# starduino.net
KiCad netlist of a schematic drawn in EAGLE
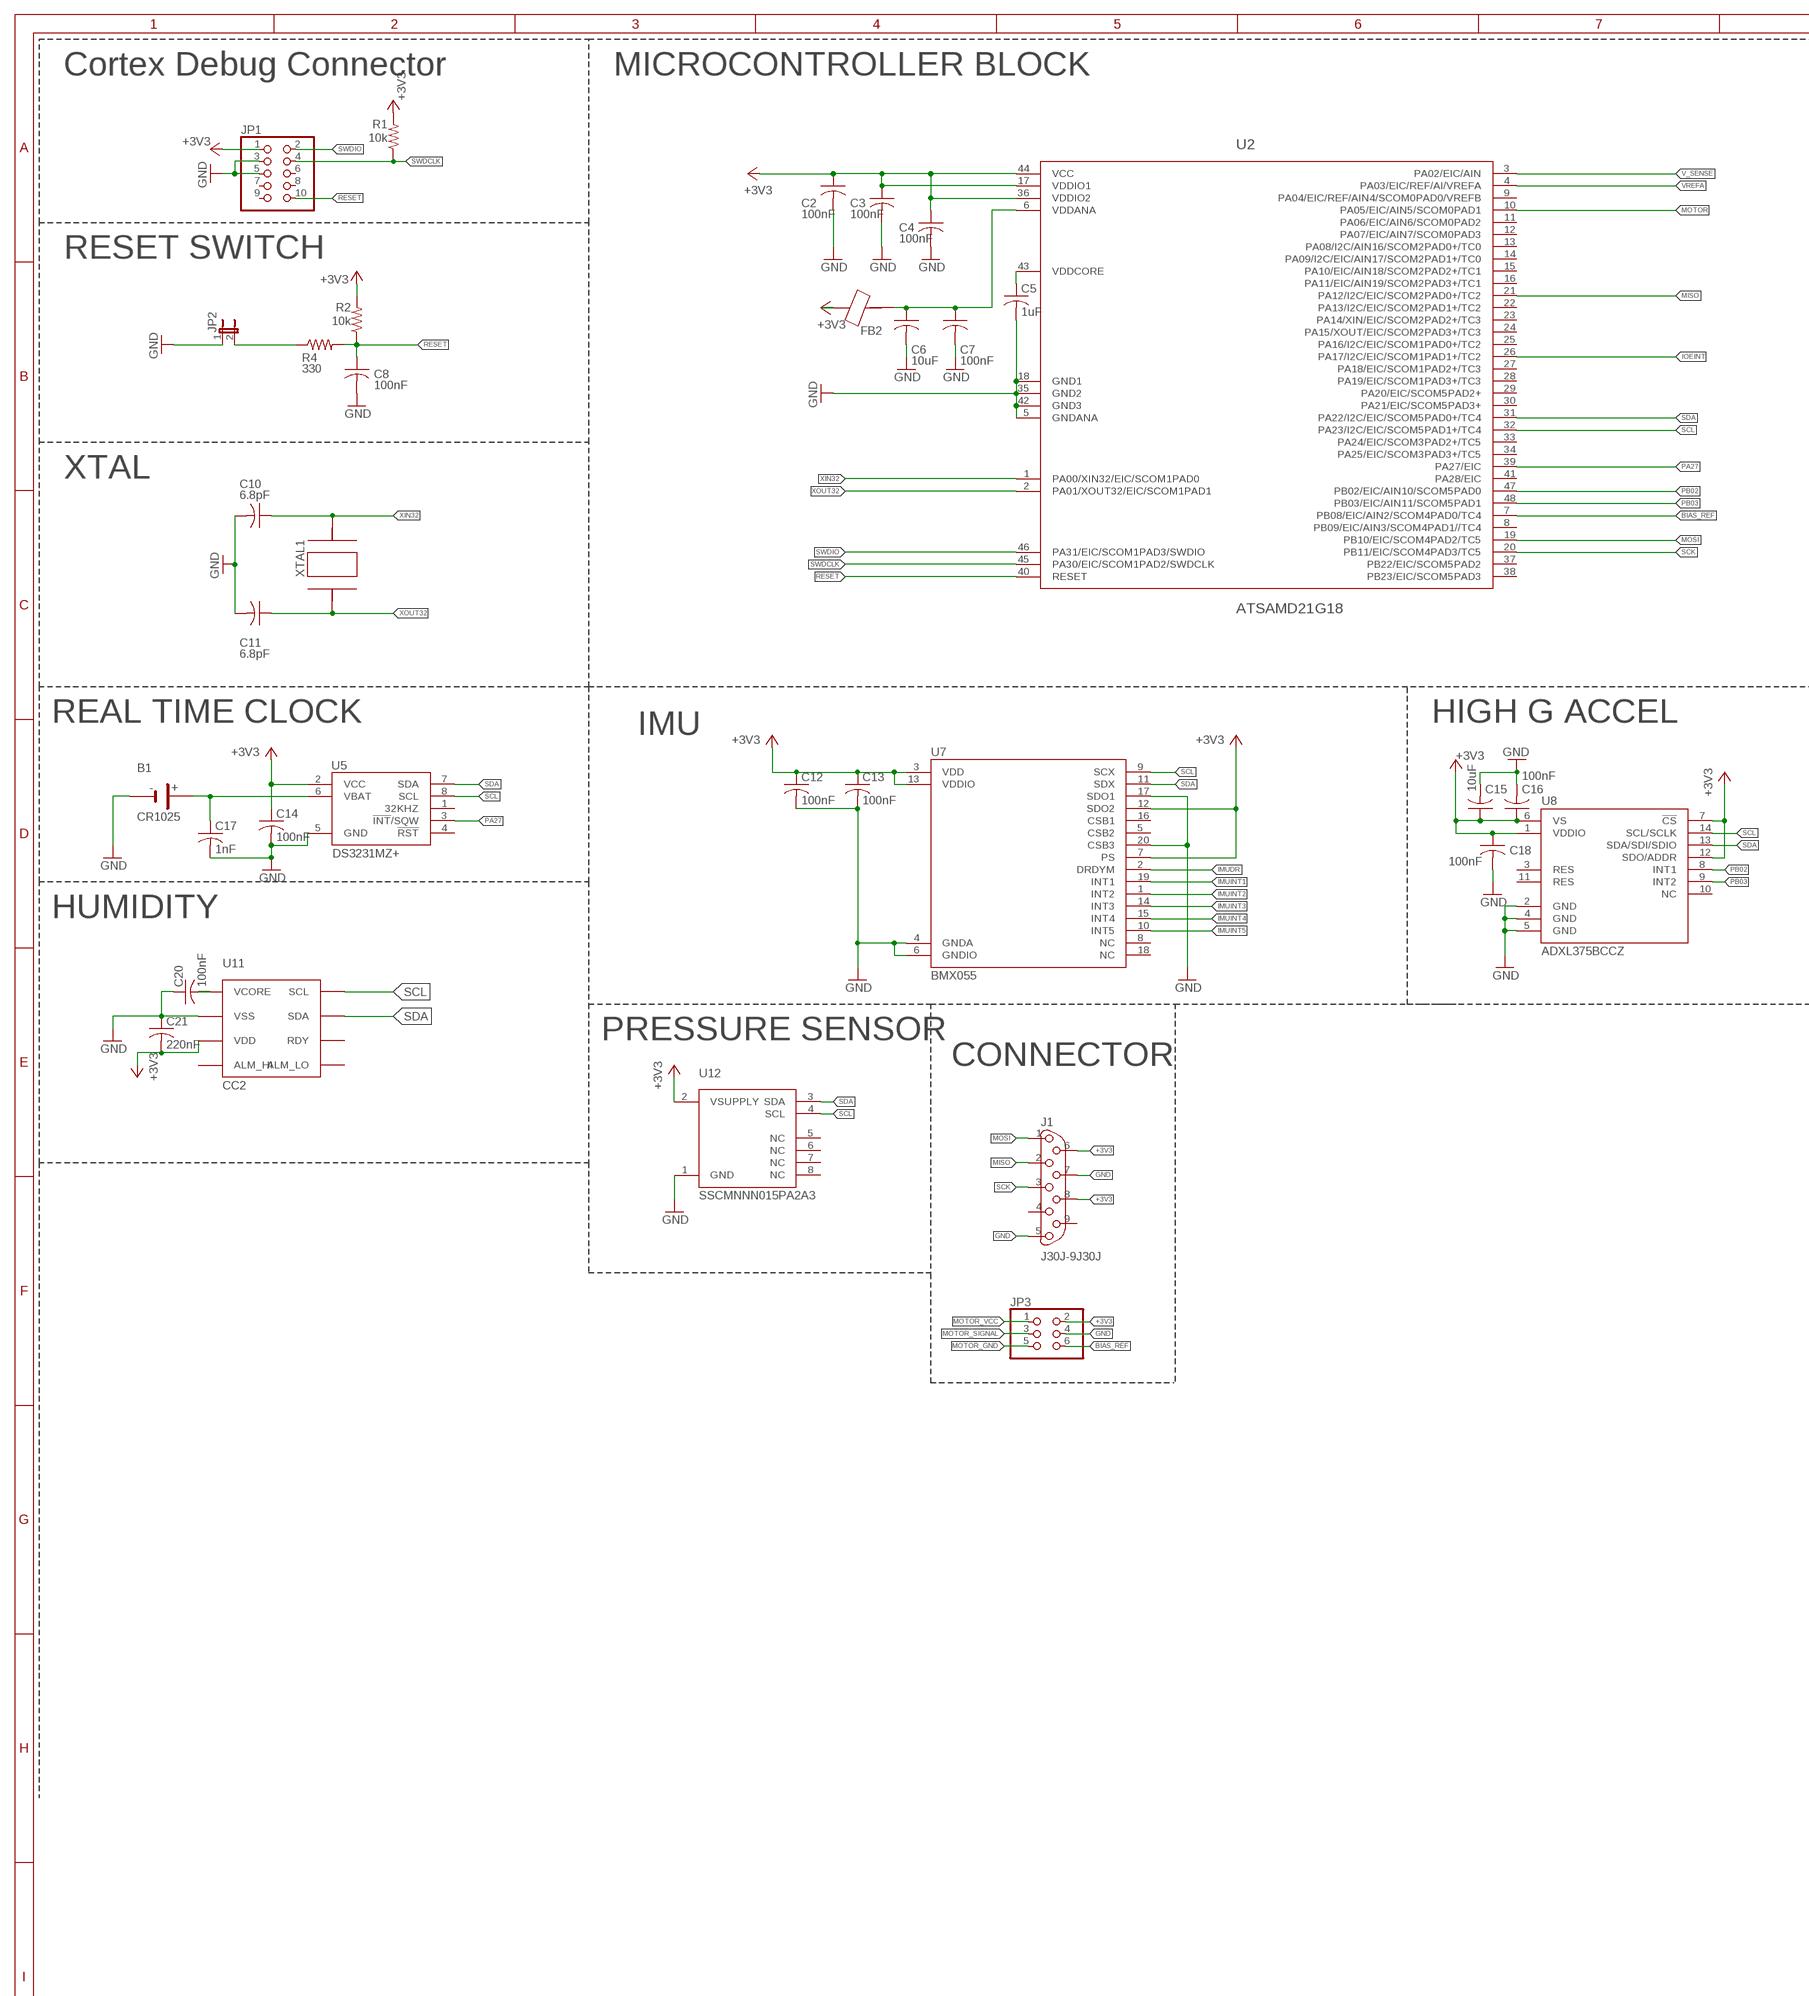
[diagram p0: schematic, sheet 1, part 1 of 2]
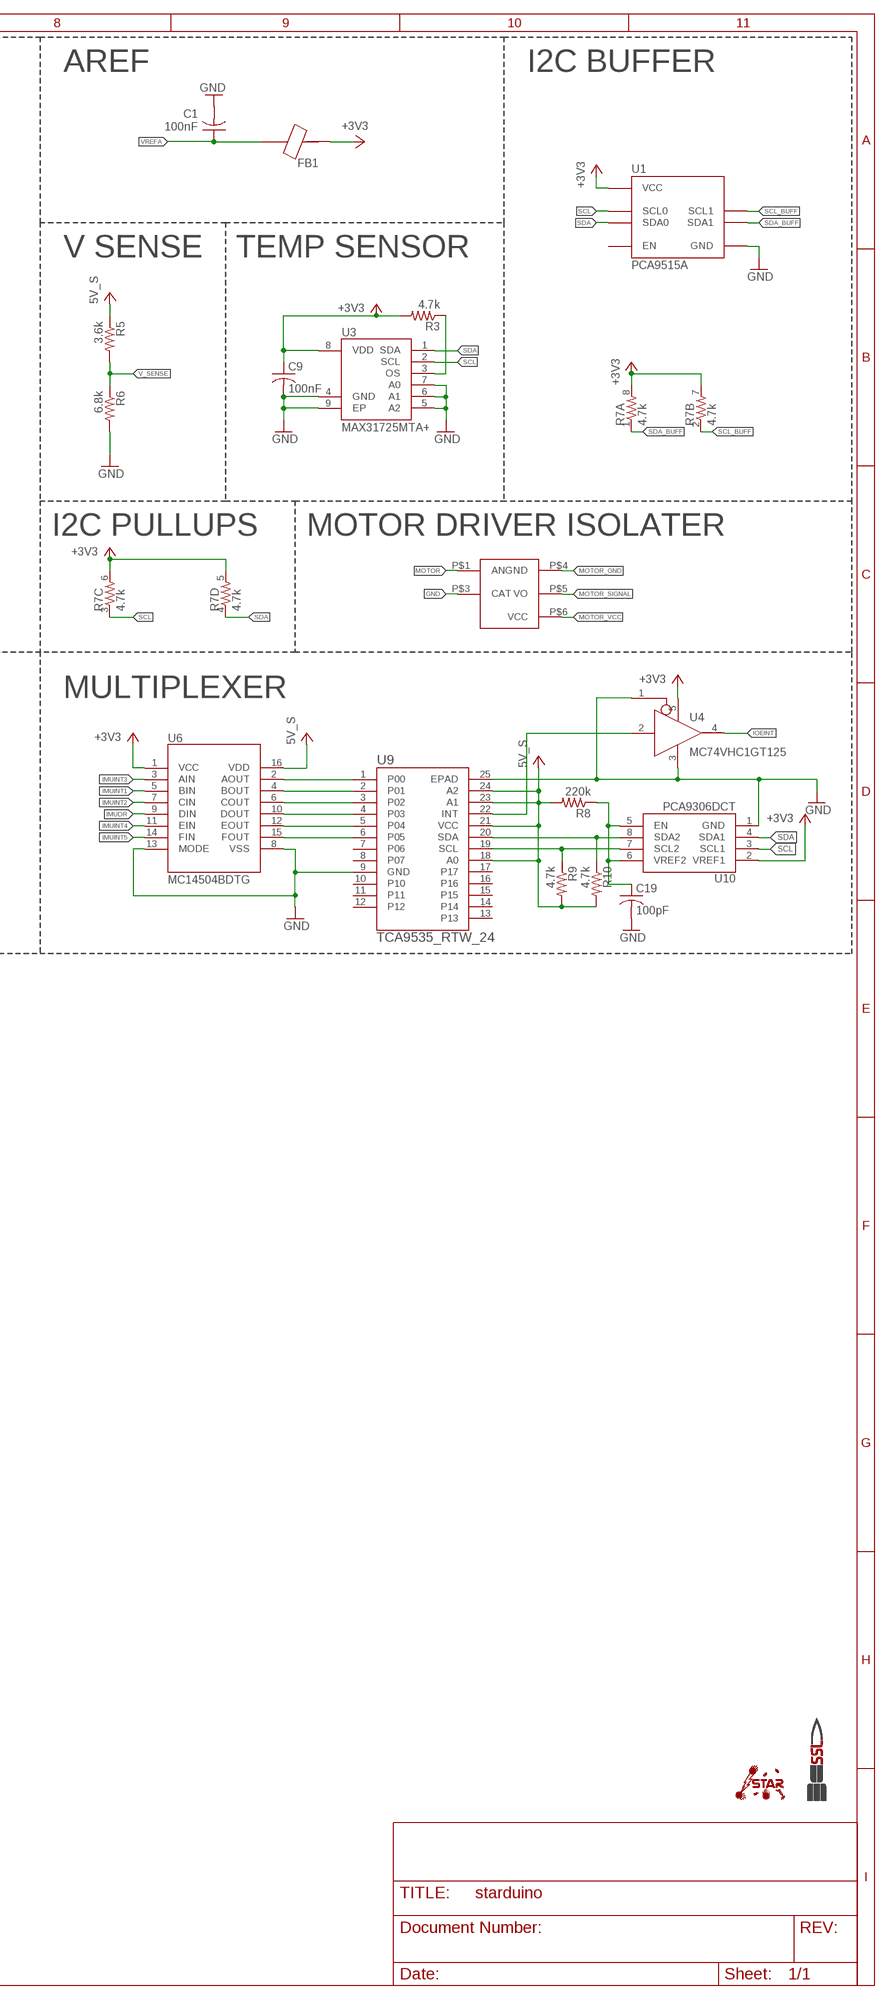
[diagram p1: schematic, sheet 1, part 2 of 2]

(export (version "E")
  (design (tool "Eeschema 10.0.6"))
  (components
    (comp (ref "B1")
      (value "CR1025")
      (footprint "eagle-import:CR1025")
      (libsource (lib "eagle-import") (part "CR1025"))
    )
    (comp (ref "C1")
      (value "100nF")
      (footprint "eagle-import:C0603")
      (libsource (lib "eagle-import") (part "resistor_C-USC0603"))
    )
    (comp (ref "C2")
      (value "100nF")
      (footprint "eagle-import:C0603")
      (libsource (lib "eagle-import") (part "resistor_C-USC0603"))
    )
    (comp (ref "C3")
      (value "100nF")
      (footprint "eagle-import:C0603")
      (libsource (lib "eagle-import") (part "resistor_C-USC0603"))
    )
    (comp (ref "C4")
      (value "100nF")
      (footprint "eagle-import:C0603")
      (libsource (lib "eagle-import") (part "resistor_C-USC0603"))
    )
    (comp (ref "C5")
      (value "1uF")
      (footprint "eagle-import:C0603")
      (libsource (lib "eagle-import") (part "resistor_C-USC0603"))
    )
    (comp (ref "C6")
      (value "10uF")
      (footprint "eagle-import:C0603")
      (libsource (lib "eagle-import") (part "resistor_C-USC0603"))
    )
    (comp (ref "C7")
      (value "100nF")
      (footprint "eagle-import:C0603")
      (libsource (lib "eagle-import") (part "resistor_C-USC0603"))
    )
    (comp (ref "C8")
      (value "100nF")
      (footprint "eagle-import:C0603")
      (libsource (lib "eagle-import") (part "resistor_C-USC0603"))
    )
    (comp (ref "C9")
      (value "100nF")
      (footprint "eagle-import:C0603")
      (libsource (lib "eagle-import") (part "resistor_C-USC0603"))
    )
    (comp (ref "C10")
      (value "6.8pF")
      (footprint "eagle-import:C0603")
      (libsource (lib "eagle-import") (part "resistor_C-USC0603"))
    )
    (comp (ref "C11")
      (value "6.8pF")
      (footprint "eagle-import:C0603")
      (libsource (lib "eagle-import") (part "resistor_C-USC0603"))
    )
    (comp (ref "C12")
      (value "100nF")
      (footprint "eagle-import:C0603")
      (libsource (lib "eagle-import") (part "resistor_C-USC0603"))
    )
    (comp (ref "C13")
      (value "100nF")
      (footprint "eagle-import:C0603")
      (libsource (lib "eagle-import") (part "resistor_C-USC0603"))
    )
    (comp (ref "C14")
      (value "100nF")
      (footprint "eagle-import:C0603")
      (libsource (lib "eagle-import") (part "resistor_C-USC0603"))
    )
    (comp (ref "C15")
      (value "10uF")
      (footprint "eagle-import:C0603")
      (libsource (lib "eagle-import") (part "resistor_C-USC0603"))
    )
    (comp (ref "C16")
      (value "100nF")
      (footprint "eagle-import:C0603")
      (libsource (lib "eagle-import") (part "resistor_C-USC0603"))
    )
    (comp (ref "C17")
      (value "1nF")
      (footprint "eagle-import:C0603")
      (libsource (lib "eagle-import") (part "resistor_C-USC0603"))
    )
    (comp (ref "C18")
      (value "100nF")
      (footprint "eagle-import:C0603")
      (libsource (lib "eagle-import") (part "resistor_C-USC0603"))
    )
    (comp (ref "C19")
      (value "100pF")
      (footprint "eagle-import:C0603")
      (libsource (lib "eagle-import") (part "C-USC0603"))
    )
    (comp (ref "C20")
      (value "100nF")
      (footprint "eagle-import:C0603")
      (libsource (lib "eagle-import") (part "resistor_C-USC0603"))
    )
    (comp (ref "C21")
      (value "220nF")
      (footprint "eagle-import:C0603")
      (libsource (lib "eagle-import") (part "resistor_C-USC0603"))
    )
    (comp (ref "FB1")
      (value "BLM18KG221BH1D")
      (footprint "eagle-import:0603")
      (libsource (lib "eagle-import") (part "FERRITE_BEAD-0603"))
    )
    (comp (ref "FB2")
      (value "BLM18KG221BH1D")
      (footprint "eagle-import:0603")
      (libsource (lib "eagle-import") (part "FERRITE_BEAD-0603"))
    )
    (comp (ref "IMAG1")
      (value "SSL.3IN_SILK")
      (footprint "eagle-import:SSL_SILK_.3IN")
      (libsource (lib "eagle-import") (part "SSL.3IN_SILK"))
    )
    (comp (ref "IMAG2")
      (value "STAR")
      (footprint "eagle-import:STAR_.3IN")
      (libsource (lib "eagle-import") (part "STAR"))
    )
    (comp (ref "J1")
      (value "J30J-9J30J")
      (footprint "eagle-import:ZKN-9")
      (libsource (lib "eagle-import") (part "J30J-9J30J"))
    )
    (comp (ref "JP1")
      (value "PINHD-2X5")
      (footprint "eagle-import:2X05")
      (libsource (lib "eagle-import") (part "PINHD-2X5"))
    )
    (comp (ref "JP2")
      (value "JUMPER-2PTH")
      (footprint "eagle-import:1X02")
      (libsource (lib "eagle-import") (part "JUMPER-2PTH"))
    )
    (comp (ref "JP3")
      (value "PINHD-2X3")
      (footprint "eagle-import:2X03")
      (libsource (lib "eagle-import") (part "PINHD-2X3"))
    )
    (comp (ref "R1")
      (value "10k")
      (footprint "eagle-import:R0603")
      (libsource (lib "eagle-import") (part "resistor_R-US_R0603"))
    )
    (comp (ref "R2")
      (value "10k")
      (footprint "eagle-import:R0603")
      (libsource (lib "eagle-import") (part "resistor_R-US_R0603"))
    )
    (comp (ref "R3")
      (value "4.7k")
      (footprint "eagle-import:R0603")
      (libsource (lib "eagle-import") (part "resistor_R-US_R0603"))
    )
    (comp (ref "R4")
      (value "330")
      (footprint "eagle-import:R0603")
      (libsource (lib "eagle-import") (part "resistor_R-US_R0603"))
    )
    (comp (ref "R5")
      (value "3.6k")
      (footprint "eagle-import:R0603")
      (libsource (lib "eagle-import") (part "resistor_R-US_R0603"))
    )
    (comp (ref "R6")
      (value "6.8k")
      (footprint "eagle-import:R0603")
      (libsource (lib "eagle-import") (part "resistor_R-US_R0603"))
    )
    (comp (ref "R7")
      (value "4.7k")
      (footprint "eagle-import:0603-ARV")
      (libsource (lib "eagle-import") (part "RESISTOR-ARRAY0603-ARV"))
    )
    (comp (ref "R8")
      (value "220k")
      (footprint "eagle-import:R0603")
      (libsource (lib "eagle-import") (part "R-US_R0603"))
    )
    (comp (ref "R9")
      (value "4.7k")
      (footprint "eagle-import:R0603")
      (libsource (lib "eagle-import") (part "R-US_R0603"))
    )
    (comp (ref "R10")
      (value "4.7k")
      (footprint "eagle-import:R0603")
      (libsource (lib "eagle-import") (part "R-US_R0603"))
    )
    (comp (ref "U$1")
      (value "FODM8061-D")
      (footprint "eagle-import:SO5")
      (libsource (lib "eagle-import") (part "FODM8061-D"))
    )
    (comp (ref "U1")
      (value "PCA9515A")
      (footprint "eagle-import:TSSOP8")
      (libsource (lib "eagle-import") (part "PCA9515A"))
    )
    (comp (ref "U2")
      (value "ATSAMD21G18")
      (footprint "eagle-import:48-TQFP")
      (libsource (lib "eagle-import") (part "ATSAMD21G18"))
    )
    (comp (ref "U3")
      (value "MAX31725MTA+")
      (footprint "eagle-import:DFN-8")
      (libsource (lib "eagle-import") (part "MAX31725MTA+"))
    )
    (comp (ref "U4")
      (value "MC74VHC1GT125")
      (footprint "eagle-import:SC-70-5")
      (libsource (lib "eagle-import") (part "MC74VHC1GT125"))
    )
    (comp (ref "U5")
      (value "DS3231MZ+")
      (footprint "eagle-import:SOIC-8")
      (libsource (lib "eagle-import") (part "DS3231MZ+"))
    )
    (comp (ref "U6")
      (value "MC14504BDTG")
      (footprint "eagle-import:TSSOP16")
      (libsource (lib "eagle-import") (part "MC14504BDTG"))
    )
    (comp (ref "U7")
      (value "BMX055")
      (footprint "eagle-import:LGA-20")
      (libsource (lib "eagle-import") (part "BMX055"))
    )
    (comp (ref "U8")
      (value "ADXL375BCCZ")
      (footprint "eagle-import:LGA-14")
      (libsource (lib "eagle-import") (part "ADXL375BCCZ"))
    )
    (comp (ref "U9")
      (value "TCA9535_RTW_24")
      (footprint "eagle-import:RTW24_2P45X2P45")
      (fields (field (name "MANUFACTURER_PART_NUMBER") "tca9535_rtw_24"))
      (libsource (lib "eagle-import") (part "TCA9535_RTW_24"))
    )
    (comp (ref "U10")
      (value "PCA9306DCT")
      (footprint "eagle-import:SSOP8")
      (libsource (lib "eagle-import") (part "PCA9306DCT"))
    )
    (comp (ref "U11")
      (value "CC2")
      (footprint "eagle-import:CC2")
      (libsource (lib "eagle-import") (part "CC2"))
    )
    (comp (ref "U12")
      (value "SSCMNNN015PA2A3")
      (footprint "eagle-import:HSC-SMT-8")
      (libsource (lib "eagle-import") (part "SSCMNNN015PA2A3"))
    )
    (comp (ref "XTAL1")
      (value "ABS07AIG-32.768KHZ-1-T")
      (footprint "eagle-import:2-SMD")
      (libsource (lib "eagle-import") (part "ABS07AIG-32.768KHZ-1-T"))
    )
  )
  (nets
    (net (code "1") (name "+3V3") (class "Default")
      (node (ref "C12") (pin "1") (pinfunction "1_1") (pintype "passive"))
      (node (ref "C13") (pin "1") (pinfunction "1_1") (pintype "passive"))
      (node (ref "C14") (pin "1") (pinfunction "1_1") (pintype "passive"))
      (node (ref "C15") (pin "1") (pinfunction "1_1") (pintype "passive"))
      (node (ref "C16") (pin "1") (pinfunction "1_1") (pintype "passive"))
      (node (ref "C18") (pin "1") (pinfunction "1_1") (pintype "passive"))
      (node (ref "C2") (pin "1") (pinfunction "1_1") (pintype "passive"))
      (node (ref "C21") (pin "2") (pinfunction "2_2") (pintype "passive"))
      (node (ref "C3") (pin "1") (pinfunction "1_1") (pintype "passive"))
      (node (ref "C4") (pin "1") (pinfunction "1_1") (pintype "passive"))
      (node (ref "C9") (pin "1") (pinfunction "1_1") (pintype "passive"))
      (node (ref "FB1") (pin "2") (pinfunction "P$2_2") (pintype "passive"))
      (node (ref "FB2") (pin "1") (pinfunction "P$1_1") (pintype "passive"))
      (node (ref "J1") (pin "6") (pinfunction "6_6") (pintype "bidirectional"))
      (node (ref "J1") (pin "8") (pinfunction "8_8") (pintype "bidirectional"))
      (node (ref "JP1") (pin "1") (pinfunction "1_1") (pintype "passive"))
      (node (ref "JP3") (pin "2") (pinfunction "2_2") (pintype "passive"))
      (node (ref "R1") (pin "2") (pinfunction "2_2") (pintype "passive"))
      (node (ref "R2") (pin "2") (pinfunction "2_2") (pintype "passive"))
      (node (ref "R3") (pin "2") (pinfunction "2_2") (pintype "passive"))
      (node (ref "R7") (pin "5") (pinfunction "2_5") (pintype "passive"))
      (node (ref "R7") (pin "6") (pinfunction "2_6") (pintype "passive"))
      (node (ref "R7") (pin "7") (pinfunction "2_7") (pintype "passive"))
      (node (ref "R7") (pin "8") (pinfunction "2_8") (pintype "passive"))
      (node (ref "U1") (pin "P$8") (pinfunction "VCC_P$8") (pintype "bidirectional"))
      (node (ref "U10") (pin "2") (pinfunction "VREF1_2") (pintype "power_in"))
      (node (ref "U11") (pin "P$7") (pinfunction "VDD_P$7") (pintype "power_in"))
      (node (ref "U12") (pin "2") (pinfunction "VSUPPLY_2") (pintype "power_in"))
      (node (ref "U2") (pin "17") (pinfunction "VDDIO1_17") (pintype "bidirectional"))
      (node (ref "U2") (pin "36") (pinfunction "VDDIO2_36") (pintype "bidirectional"))
      (node (ref "U2") (pin "44") (pinfunction "VCC_44") (pintype "bidirectional"))
      (node (ref "U3") (pin "8") (pinfunction "VDD_8") (pintype "power_in"))
      (node (ref "U4") (pin "5") (pinfunction "VIN_5") (pintype "bidirectional"))
      (node (ref "U5") (pin "2") (pinfunction "VCC_2") (pintype "power_in"))
      (node (ref "U6") (pin "1") (pinfunction "VCC_1") (pintype "power_in"))
      (node (ref "U7") (pin "12") (pinfunction "SDO2_12") (pintype "bidirectional"))
      (node (ref "U7") (pin "13") (pinfunction "VDDIO_13") (pintype "power_in"))
      (node (ref "U7") (pin "3") (pinfunction "VDD_3") (pintype "power_in"))
      (node (ref "U7") (pin "7") (pinfunction "PS_7") (pintype "bidirectional"))
      (node (ref "U8") (pin "1") (pinfunction "VDDIO_1") (pintype "bidirectional"))
      (node (ref "U8") (pin "12") (pinfunction "SDO/ADDR_12") (pintype "bidirectional"))
      (node (ref "U8") (pin "6") (pinfunction "VS_6") (pintype "bidirectional"))
      (node (ref "U8") (pin "7") (pinfunction "~{CS}_7") (pintype "bidirectional"))
    )
    (net (code "2") (name "5V_S") (class "Default")
      (node (ref "R10") (pin "2") (pinfunction "2_2") (pintype "passive"))
      (node (ref "R5") (pin "1") (pinfunction "1_1") (pintype "passive"))
      (node (ref "R8") (pin "2") (pinfunction "2_2") (pintype "passive"))
      (node (ref "R9") (pin "2") (pinfunction "2_2") (pintype "passive"))
      (node (ref "U6") (pin "16") (pinfunction "VDD_16") (pintype "power_in"))
      (node (ref "U9") (pin "18") (pinfunction "A0_18") (pintype "input"))
      (node (ref "U9") (pin "21") (pinfunction "VCC_21") (pintype "power_in"))
      (node (ref "U9") (pin "23") (pinfunction "A1_23") (pintype "input"))
      (node (ref "U9") (pin "24") (pinfunction "A2_24") (pintype "input"))
    )
    (net (code "3") (name "BIAS_REF") (class "Default")
      (node (ref "JP3") (pin "6") (pinfunction "6_6") (pintype "passive"))
      (node (ref "U2") (pin "7") (pinfunction "PB08/EIC/AIN2/SCOM4PAD0/TC4_7") (pintype "bidirectional"))
    )
    (net (code "4") (name "GND") (class "Default")
      (node (ref "B1") (pin "3") (pinfunction "-_3") (pintype "power_in"))
      (node (ref "C1") (pin "2") (pinfunction "2_2") (pintype "passive"))
      (node (ref "C10") (pin "2") (pinfunction "2_2") (pintype "passive"))
      (node (ref "C11") (pin "2") (pinfunction "2_2") (pintype "passive"))
      (node (ref "C12") (pin "2") (pinfunction "2_2") (pintype "passive"))
      (node (ref "C13") (pin "2") (pinfunction "2_2") (pintype "passive"))
      (node (ref "C14") (pin "2") (pinfunction "2_2") (pintype "passive"))
      (node (ref "C15") (pin "2") (pinfunction "2_2") (pintype "passive"))
      (node (ref "C16") (pin "2") (pinfunction "2_2") (pintype "passive"))
      (node (ref "C17") (pin "2") (pinfunction "2_2") (pintype "passive"))
      (node (ref "C18") (pin "2") (pinfunction "2_2") (pintype "passive"))
      (node (ref "C19") (pin "2") (pinfunction "2_2") (pintype "passive"))
      (node (ref "C2") (pin "2") (pinfunction "2_2") (pintype "passive"))
      (node (ref "C20") (pin "1") (pinfunction "1_1") (pintype "passive"))
      (node (ref "C21") (pin "1") (pinfunction "1_1") (pintype "passive"))
      (node (ref "C3") (pin "2") (pinfunction "2_2") (pintype "passive"))
      (node (ref "C4") (pin "2") (pinfunction "2_2") (pintype "passive"))
      (node (ref "C5") (pin "2") (pinfunction "2_2") (pintype "passive"))
      (node (ref "C6") (pin "2") (pinfunction "2_2") (pintype "passive"))
      (node (ref "C7") (pin "2") (pinfunction "2_2") (pintype "passive"))
      (node (ref "C8") (pin "2") (pinfunction "2_2") (pintype "passive"))
      (node (ref "C9") (pin "2") (pinfunction "2_2") (pintype "passive"))
      (node (ref "J1") (pin "5") (pinfunction "5_5") (pintype "bidirectional"))
      (node (ref "J1") (pin "7") (pinfunction "7_7") (pintype "bidirectional"))
      (node (ref "JP1") (pin "3") (pinfunction "3_3") (pintype "passive"))
      (node (ref "JP1") (pin "5") (pinfunction "5_5") (pintype "passive"))
      (node (ref "JP2") (pin "1") (pinfunction "1_1") (pintype "passive"))
      (node (ref "JP3") (pin "4") (pinfunction "4_4") (pintype "passive"))
      (node (ref "R6") (pin "2") (pinfunction "2_2") (pintype "passive"))
      (node (ref "U$1") (pin "P$3") (pinfunction "CAT_P$3") (pintype "bidirectional"))
      (node (ref "U1") (pin "P$4") (pinfunction "GND_P$4") (pintype "bidirectional"))
      (node (ref "U10") (pin "1") (pinfunction "GND_1") (pintype "power_in"))
      (node (ref "U11") (pin "P$6") (pinfunction "VSS_P$6") (pintype "power_in"))
      (node (ref "U12") (pin "1") (pinfunction "GND_1") (pintype "power_in"))
      (node (ref "U2") (pin "18") (pinfunction "GND1_18") (pintype "bidirectional"))
      (node (ref "U2") (pin "35") (pinfunction "GND2_35") (pintype "bidirectional"))
      (node (ref "U2") (pin "42") (pinfunction "GND3_42") (pintype "bidirectional"))
      (node (ref "U2") (pin "5") (pinfunction "GNDANA_5") (pintype "bidirectional"))
      (node (ref "U3") (pin "4") (pinfunction "GND_4") (pintype "power_in"))
      (node (ref "U3") (pin "5") (pinfunction "A2_5") (pintype "bidirectional"))
      (node (ref "U3") (pin "6") (pinfunction "A1_6") (pintype "bidirectional"))
      (node (ref "U3") (pin "7") (pinfunction "A0_7") (pintype "bidirectional"))
      (node (ref "U3") (pin "9") (pinfunction "EP_9") (pintype "power_in"))
      (node (ref "U4") (pin "1") (pinfunction "OE_1") (pintype "bidirectional"))
      (node (ref "U4") (pin "3") (pinfunction "GND_3") (pintype "bidirectional"))
      (node (ref "U5") (pin "5") (pinfunction "GND_5") (pintype "power_in"))
      (node (ref "U6") (pin "13") (pinfunction "MODE_13") (pintype "input"))
      (node (ref "U6") (pin "8") (pinfunction "VSS_8") (pintype "power_in"))
      (node (ref "U7") (pin "17") (pinfunction "SDO1_17") (pintype "bidirectional"))
      (node (ref "U7") (pin "20") (pinfunction "CSB3_20") (pintype "bidirectional"))
      (node (ref "U7") (pin "4") (pinfunction "GNDA_4") (pintype "power_in"))
      (node (ref "U7") (pin "6") (pinfunction "GNDIO_6") (pintype "power_in"))
      (node (ref "U8") (pin "2") (pinfunction "GND_2") (pintype "bidirectional"))
      (node (ref "U8") (pin "4") (pinfunction "GND_4") (pintype "bidirectional"))
      (node (ref "U8") (pin "5") (pinfunction "GND_5") (pintype "bidirectional"))
      (node (ref "U9") (pin "25") (pinfunction "EPAD_25") (pintype "passive"))
      (node (ref "U9") (pin "9") (pinfunction "GND_9") (pintype "power_in"))
    )
    (net (code "5") (name "IMUDR") (class "Default")
      (node (ref "U6") (pin "9") (pinfunction "DIN_9") (pintype "input"))
      (node (ref "U7") (pin "2") (pinfunction "DRDYM_2") (pintype "bidirectional"))
    )
    (net (code "6") (name "IMUINT1") (class "Default")
      (node (ref "U6") (pin "5") (pinfunction "BIN_5") (pintype "input"))
      (node (ref "U7") (pin "19") (pinfunction "INT1_19") (pintype "bidirectional"))
    )
    (net (code "7") (name "IMUINT2") (class "Default")
      (node (ref "U6") (pin "7") (pinfunction "CIN_7") (pintype "input"))
      (node (ref "U7") (pin "1") (pinfunction "INT2_1") (pintype "bidirectional"))
    )
    (net (code "8") (name "IMUINT3") (class "Default")
      (node (ref "U6") (pin "3") (pinfunction "AIN_3") (pintype "input"))
      (node (ref "U7") (pin "14") (pinfunction "INT3_14") (pintype "bidirectional"))
    )
    (net (code "9") (name "IMUINT4") (class "Default")
      (node (ref "U6") (pin "11") (pinfunction "EIN_11") (pintype "input"))
      (node (ref "U7") (pin "15") (pinfunction "INT4_15") (pintype "bidirectional"))
    )
    (net (code "10") (name "IMUINT5") (class "Default")
      (node (ref "U6") (pin "14") (pinfunction "FIN_14") (pintype "input"))
      (node (ref "U7") (pin "10") (pinfunction "INT5_10") (pintype "bidirectional"))
    )
    (net (code "11") (name "IOEINT") (class "Default")
      (node (ref "U2") (pin "26") (pinfunction "PA17/I2C/EIC/SCOM1PAD1+/TC2_26") (pintype "bidirectional"))
      (node (ref "U4") (pin "4") (pinfunction "Y_4") (pintype "bidirectional"))
    )
    (net (code "12") (name "MISO") (class "Default")
      (node (ref "J1") (pin "2") (pinfunction "2_2") (pintype "bidirectional"))
      (node (ref "U2") (pin "21") (pinfunction "PA12/I2C/EIC/SCOM2PAD0+/TC2_21") (pintype "bidirectional"))
    )
    (net (code "13") (name "MOSI") (class "Default")
      (node (ref "J1") (pin "1") (pinfunction "1_1") (pintype "bidirectional"))
      (node (ref "U2") (pin "19") (pinfunction "PB10/EIC/SCOM4PAD2/TC5_19") (pintype "bidirectional"))
    )
    (net (code "14") (name "MOTOR") (class "Default")
      (node (ref "U$1") (pin "P$1") (pinfunction "AN_P$1") (pintype "bidirectional"))
      (node (ref "U2") (pin "10") (pinfunction "PA05/EIC/AIN5/SCOM0PAD1_10") (pintype "bidirectional"))
    )
    (net (code "15") (name "MOTOR_GND") (class "Default")
      (node (ref "JP3") (pin "5") (pinfunction "5_5") (pintype "passive"))
      (node (ref "U$1") (pin "P$4") (pinfunction "GND_P$4") (pintype "bidirectional"))
    )
    (net (code "16") (name "MOTOR_SIGNAL") (class "Default")
      (node (ref "JP3") (pin "3") (pinfunction "3_3") (pintype "passive"))
      (node (ref "U$1") (pin "P$5") (pinfunction "VO_P$5") (pintype "bidirectional"))
    )
    (net (code "17") (name "MOTOR_VCC") (class "Default")
      (node (ref "JP3") (pin "1") (pinfunction "1_1") (pintype "passive"))
      (node (ref "U$1") (pin "P$6") (pinfunction "VCC_P$6") (pintype "bidirectional"))
    )
    (net (code "18") (name "Net-(FB2-P$2)") (class "Default")
      (node (ref "C6") (pin "1") (pinfunction "1_1") (pintype "passive"))
      (node (ref "C7") (pin "1") (pinfunction "1_1") (pintype "passive"))
      (node (ref "FB2") (pin "2") (pinfunction "P$2_2") (pintype "passive"))
      (node (ref "U2") (pin "6") (pinfunction "VDDANA_6") (pintype "bidirectional"))
    )
    (net (code "19") (name "Net-(JP2-Pad2)") (class "Default")
      (node (ref "JP2") (pin "2") (pinfunction "2_2") (pintype "passive"))
      (node (ref "R4") (pin "1") (pinfunction "1_1") (pintype "passive"))
    )
    (net (code "20") (name "Net-(U2-VDDCORE)") (class "Default")
      (node (ref "C5") (pin "1") (pinfunction "1_1") (pintype "passive"))
      (node (ref "U2") (pin "43") (pinfunction "VDDCORE_43") (pintype "bidirectional"))
    )
    (net (code "21") (name "Net-(U3-OS)") (class "Default")
      (node (ref "R3") (pin "1") (pinfunction "1_1") (pintype "passive"))
      (node (ref "U3") (pin "3") (pinfunction "OS_3") (pintype "bidirectional"))
    )
    (net (code "22") (name "Net-(U4-A)") (class "Default")
      (node (ref "U4") (pin "2") (pinfunction "A_2") (pintype "bidirectional"))
      (node (ref "U9") (pin "22") (pinfunction "INT_22") (pintype "output"))
    )
    (net (code "23") (name "Net-(U5-VBAT)") (class "Default")
      (node (ref "B1") (pin "1") (pinfunction "+_1") (pintype "power_in"))
      (node (ref "B1") (pin "2") (pinfunction "+_2") (pintype "power_in"))
      (node (ref "C17") (pin "1") (pinfunction "1_1") (pintype "passive"))
      (node (ref "U5") (pin "6") (pinfunction "VBAT_6") (pintype "power_in"))
    )
    (net (code "24") (name "Net-(U6-AOUT)") (class "Default")
      (node (ref "U6") (pin "2") (pinfunction "AOUT_2") (pintype "output"))
      (node (ref "U9") (pin "1") (pinfunction "P00_1") (pintype "bidirectional"))
    )
    (net (code "25") (name "Net-(U6-BOUT)") (class "Default")
      (node (ref "U6") (pin "4") (pinfunction "BOUT_4") (pintype "output"))
      (node (ref "U9") (pin "2") (pinfunction "P01_2") (pintype "bidirectional"))
    )
    (net (code "26") (name "Net-(U6-COUT)") (class "Default")
      (node (ref "U6") (pin "6") (pinfunction "COUT_6") (pintype "output"))
      (node (ref "U9") (pin "3") (pinfunction "P02_3") (pintype "bidirectional"))
    )
    (net (code "27") (name "Net-(U6-DOUT)") (class "Default")
      (node (ref "U6") (pin "10") (pinfunction "DOUT_10") (pintype "output"))
      (node (ref "U9") (pin "4") (pinfunction "P03_4") (pintype "bidirectional"))
    )
    (net (code "28") (name "Net-(U6-EOUT)") (class "Default")
      (node (ref "U6") (pin "12") (pinfunction "EOUT_12") (pintype "output"))
      (node (ref "U9") (pin "5") (pinfunction "P04_5") (pintype "bidirectional"))
    )
    (net (code "29") (name "Net-(U6-FOUT)") (class "Default")
      (node (ref "U6") (pin "15") (pinfunction "FOUT_15") (pintype "output"))
      (node (ref "U9") (pin "6") (pinfunction "P05_6") (pintype "bidirectional"))
    )
    (net (code "30") (name "Net-(U10-EN)") (class "Default")
      (node (ref "C19") (pin "1") (pinfunction "1_1") (pintype "passive"))
      (node (ref "R8") (pin "1") (pinfunction "1_1") (pintype "passive"))
      (node (ref "U10") (pin "5") (pinfunction "EN_5") (pintype "input"))
      (node (ref "U10") (pin "6") (pinfunction "VREF2_6") (pintype "power_in"))
    )
    (net (code "31") (name "Net-(U10-SCL2)") (class "Default")
      (node (ref "R9") (pin "1") (pinfunction "1_1") (pintype "passive"))
      (node (ref "U10") (pin "7") (pinfunction "SCL2_7") (pintype "bidirectional"))
      (node (ref "U9") (pin "19") (pinfunction "SCL_19") (pintype "bidirectional"))
    )
    (net (code "32") (name "Net-(U10-SDA2)") (class "Default")
      (node (ref "R10") (pin "1") (pinfunction "1_1") (pintype "passive"))
      (node (ref "U10") (pin "8") (pinfunction "SDA2_8") (pintype "bidirectional"))
      (node (ref "U9") (pin "20") (pinfunction "SDA_20") (pintype "bidirectional"))
    )
    (net (code "33") (name "Net-(U11-VCORE)") (class "Default")
      (node (ref "C20") (pin "2") (pinfunction "2_2") (pintype "passive"))
      (node (ref "U11") (pin "P$5") (pinfunction "VCORE_P$5") (pintype "power_in"))
    )
    (net (code "34") (name "PA27") (class "Default")
      (node (ref "U2") (pin "39") (pinfunction "PA27/EIC_39") (pintype "bidirectional"))
      (node (ref "U5") (pin "3") (pinfunction "~{INT}/SQW_3") (pintype "bidirectional"))
    )
    (net (code "35") (name "PB02") (class "Default")
      (node (ref "U2") (pin "47") (pinfunction "PB02/EIC/AIN10/SCOM5PAD0_47") (pintype "bidirectional"))
      (node (ref "U8") (pin "8") (pinfunction "INT1_8") (pintype "bidirectional"))
    )
    (net (code "36") (name "PB03") (class "Default")
      (node (ref "U2") (pin "48") (pinfunction "PB03/EIC/AIN11/SCOM5PAD1_48") (pintype "bidirectional"))
      (node (ref "U8") (pin "9") (pinfunction "INT2_9") (pintype "bidirectional"))
    )
    (net (code "37") (name "RESET") (class "Default")
      (node (ref "C8") (pin "1") (pinfunction "1_1") (pintype "passive"))
      (node (ref "JP1") (pin "10") (pinfunction "10_10") (pintype "passive"))
      (node (ref "R2") (pin "1") (pinfunction "1_1") (pintype "passive"))
      (node (ref "R4") (pin "2") (pinfunction "2_2") (pintype "passive"))
      (node (ref "U2") (pin "40") (pinfunction "RESET_40") (pintype "bidirectional"))
    )
    (net (code "38") (name "SCK") (class "Default")
      (node (ref "J1") (pin "3") (pinfunction "3_3") (pintype "bidirectional"))
      (node (ref "U2") (pin "20") (pinfunction "PB11/EIC/SCOM4PAD3/TC5_20") (pintype "bidirectional"))
    )
    (net (code "39") (name "SCL") (class "Default")
      (node (ref "R7") (pin "3") (pinfunction "1_3") (pintype "passive"))
      (node (ref "U1") (pin "P$2") (pinfunction "SCL0_P$2") (pintype "bidirectional"))
      (node (ref "U10") (pin "3") (pinfunction "SCL1_3") (pintype "bidirectional"))
      (node (ref "U11") (pin "P$4") (pinfunction "SCL_P$4") (pintype "bidirectional"))
      (node (ref "U12") (pin "4") (pinfunction "SCL_4") (pintype "bidirectional"))
      (node (ref "U2") (pin "32") (pinfunction "PA23/I2C/EIC/SCOM5PAD1+/TC4_32") (pintype "bidirectional"))
      (node (ref "U3") (pin "2") (pinfunction "SCL_2") (pintype "bidirectional"))
      (node (ref "U5") (pin "8") (pinfunction "SCL_8") (pintype "bidirectional"))
      (node (ref "U7") (pin "9") (pinfunction "SCX_9") (pintype "bidirectional"))
      (node (ref "U8") (pin "14") (pinfunction "SCL/SCLK_14") (pintype "bidirectional"))
    )
    (net (code "40") (name "SCL_BUFF") (class "Default")
      (node (ref "R7") (pin "2") (pinfunction "1_2") (pintype "passive"))
      (node (ref "U1") (pin "P$7") (pinfunction "SCL1_P$7") (pintype "bidirectional"))
    )
    (net (code "41") (name "SDA") (class "Default")
      (node (ref "R7") (pin "4") (pinfunction "1_4") (pintype "passive"))
      (node (ref "U1") (pin "P$3") (pinfunction "SDA0_P$3") (pintype "bidirectional"))
      (node (ref "U10") (pin "4") (pinfunction "SDA1_4") (pintype "bidirectional"))
      (node (ref "U11") (pin "P$3") (pinfunction "SDA_P$3") (pintype "bidirectional"))
      (node (ref "U12") (pin "3") (pinfunction "SDA_3") (pintype "bidirectional"))
      (node (ref "U2") (pin "31") (pinfunction "PA22/I2C/EIC/SCOM5PAD0+/TC4_31") (pintype "bidirectional"))
      (node (ref "U3") (pin "1") (pinfunction "SDA_1") (pintype "bidirectional"))
      (node (ref "U5") (pin "7") (pinfunction "SDA_7") (pintype "bidirectional"))
      (node (ref "U7") (pin "11") (pinfunction "SDX_11") (pintype "bidirectional"))
      (node (ref "U8") (pin "13") (pinfunction "SDA/SDI/SDIO_13") (pintype "bidirectional"))
    )
    (net (code "42") (name "SDA_BUFF") (class "Default")
      (node (ref "R7") (pin "1") (pinfunction "1_1") (pintype "passive"))
      (node (ref "U1") (pin "P$6") (pinfunction "SDA1_P$6") (pintype "bidirectional"))
    )
    (net (code "43") (name "SWDCLK") (class "Default")
      (node (ref "JP1") (pin "4") (pinfunction "4_4") (pintype "passive"))
      (node (ref "R1") (pin "1") (pinfunction "1_1") (pintype "passive"))
      (node (ref "U2") (pin "45") (pinfunction "PA30/EIC/SCOM1PAD2/SWDCLK_45") (pintype "bidirectional"))
    )
    (net (code "44") (name "SWDIO") (class "Default")
      (node (ref "JP1") (pin "2") (pinfunction "2_2") (pintype "passive"))
      (node (ref "U2") (pin "46") (pinfunction "PA31/EIC/SCOM1PAD3/SWDIO_46") (pintype "bidirectional"))
    )
    (net (code "45") (name "VREFA") (class "Default")
      (node (ref "C1") (pin "1") (pinfunction "1_1") (pintype "passive"))
      (node (ref "FB1") (pin "1") (pinfunction "P$1_1") (pintype "passive"))
      (node (ref "U2") (pin "4") (pinfunction "PA03/EIC/REF/AI/VREFA_4") (pintype "bidirectional"))
    )
    (net (code "46") (name "V_SENSE") (class "Default")
      (node (ref "R5") (pin "2") (pinfunction "2_2") (pintype "passive"))
      (node (ref "R6") (pin "1") (pinfunction "1_1") (pintype "passive"))
      (node (ref "U2") (pin "3") (pinfunction "PA02/EIC/AIN_3") (pintype "bidirectional"))
    )
    (net (code "47") (name "XIN32") (class "Default")
      (node (ref "C10") (pin "1") (pinfunction "1_1") (pintype "passive"))
      (node (ref "U2") (pin "1") (pinfunction "PA00/XIN32/EIC/SCOM1PAD0_1") (pintype "bidirectional"))
      (node (ref "XTAL1") (pin "P2") (pinfunction "2_P2") (pintype "bidirectional"))
    )
    (net (code "48") (name "XOUT32") (class "Default")
      (node (ref "C11") (pin "1") (pinfunction "1_1") (pintype "passive"))
      (node (ref "U2") (pin "2") (pinfunction "PA01/XOUT32/EIC/SCOM1PAD1_2") (pintype "bidirectional"))
      (node (ref "XTAL1") (pin "P1") (pinfunction "1_P1") (pintype "bidirectional"))
    )
    (net (code "49") (name "unconnected-(J1-Pad4)") (class "Default")
      (node (ref "J1") (pin "4") (pinfunction "4_4") (pintype "bidirectional"))
    )
    (net (code "50") (name "unconnected-(J1-Pad9)") (class "Default")
      (node (ref "J1") (pin "9") (pinfunction "9_9") (pintype "bidirectional"))
    )
    (net (code "51") (name "unconnected-(JP1-Pad6)") (class "Default")
      (node (ref "JP1") (pin "6") (pinfunction "6_6") (pintype "passive"))
    )
    (net (code "52") (name "unconnected-(JP1-Pad7)") (class "Default")
      (node (ref "JP1") (pin "7") (pinfunction "7_7") (pintype "passive"))
    )
    (net (code "53") (name "unconnected-(JP1-Pad8)") (class "Default")
      (node (ref "JP1") (pin "8") (pinfunction "8_8") (pintype "passive"))
    )
    (net (code "54") (name "unconnected-(JP1-Pad9)") (class "Default")
      (node (ref "JP1") (pin "9") (pinfunction "9_9") (pintype "passive"))
    )
    (net (code "55") (name "unconnected-(U1-EN-PadP$5)") (class "Default")
      (node (ref "U1") (pin "P$5") (pinfunction "EN_P$5") (pintype "bidirectional"))
    )
    (net (code "56") (name "unconnected-(U2-PA04{slash}EIC{slash}REF{slash}AIN4{slash}SCOM0PAD0{slash}VREFB-Pad9)") (class "Default")
      (node (ref "U2") (pin "9") (pinfunction "PA04/EIC/REF/AIN4/SCOM0PAD0/VREFB_9") (pintype "bidirectional"))
    )
    (net (code "57") (name "unconnected-(U2-PA06{slash}EIC{slash}AIN6{slash}SCOM0PAD2-Pad11)") (class "Default")
      (node (ref "U2") (pin "11") (pinfunction "PA06/EIC/AIN6/SCOM0PAD2_11") (pintype "bidirectional"))
    )
    (net (code "58") (name "unconnected-(U2-PA07{slash}EIC{slash}AIN7{slash}SCOM0PAD3-Pad12)") (class "Default")
      (node (ref "U2") (pin "12") (pinfunction "PA07/EIC/AIN7/SCOM0PAD3_12") (pintype "bidirectional"))
    )
    (net (code "59") (name "unconnected-(U2-PA08{slash}I2C{slash}AIN16{slash}SCOM2PAD0+{slash}TC0-Pad13)") (class "Default")
      (node (ref "U2") (pin "13") (pinfunction "PA08/I2C/AIN16/SCOM2PAD0+/TC0_13") (pintype "bidirectional"))
    )
    (net (code "60") (name "unconnected-(U2-PA09{slash}I2C{slash}EIC{slash}AIN17{slash}SCOM2PAD1+{slash}TC0-Pad14)") (class "Default")
      (node (ref "U2") (pin "14") (pinfunction "PA09/I2C/EIC/AIN17/SCOM2PAD1+/TC0_14") (pintype "bidirectional"))
    )
    (net (code "61") (name "unconnected-(U2-PA10{slash}EIC{slash}AIN18{slash}SCOM2PAD2+{slash}TC1-Pad15)") (class "Default")
      (node (ref "U2") (pin "15") (pinfunction "PA10/EIC/AIN18/SCOM2PAD2+/TC1_15") (pintype "bidirectional"))
    )
    (net (code "62") (name "unconnected-(U2-PA11{slash}EIC{slash}AIN19{slash}SCOM2PAD3+{slash}TC1-Pad16)") (class "Default")
      (node (ref "U2") (pin "16") (pinfunction "PA11/EIC/AIN19/SCOM2PAD3+/TC1_16") (pintype "bidirectional"))
    )
    (net (code "63") (name "unconnected-(U2-PA13{slash}I2C{slash}EIC{slash}SCOM2PAD1+{slash}TC2-Pad22)") (class "Default")
      (node (ref "U2") (pin "22") (pinfunction "PA13/I2C/EIC/SCOM2PAD1+/TC2_22") (pintype "bidirectional"))
    )
    (net (code "64") (name "unconnected-(U2-PA14{slash}XIN{slash}EIC{slash}SCOM2PAD2+{slash}TC3-Pad23)") (class "Default")
      (node (ref "U2") (pin "23") (pinfunction "PA14/XIN/EIC/SCOM2PAD2+/TC3_23") (pintype "bidirectional"))
    )
    (net (code "65") (name "unconnected-(U2-PA15{slash}XOUT{slash}EIC{slash}SCOM2PAD3+{slash}TC3-Pad24)") (class "Default")
      (node (ref "U2") (pin "24") (pinfunction "PA15/XOUT/EIC/SCOM2PAD3+/TC3_24") (pintype "bidirectional"))
    )
    (net (code "66") (name "unconnected-(U2-PA16{slash}I2C{slash}EIC{slash}SCOM1PAD0+{slash}TC2-Pad25)") (class "Default")
      (node (ref "U2") (pin "25") (pinfunction "PA16/I2C/EIC/SCOM1PAD0+/TC2_25") (pintype "bidirectional"))
    )
    (net (code "67") (name "unconnected-(U2-PA18{slash}EIC{slash}SCOM1PAD2+{slash}TC3-Pad27)") (class "Default")
      (node (ref "U2") (pin "27") (pinfunction "PA18/EIC/SCOM1PAD2+/TC3_27") (pintype "bidirectional"))
    )
    (net (code "68") (name "unconnected-(U2-PA19{slash}EIC{slash}SCOM1PAD3+{slash}TC3-Pad28)") (class "Default")
      (node (ref "U2") (pin "28") (pinfunction "PA19/EIC/SCOM1PAD3+/TC3_28") (pintype "bidirectional"))
    )
    (net (code "69") (name "unconnected-(U2-PA20{slash}EIC{slash}SCOM5PAD2+-Pad29)") (class "Default")
      (node (ref "U2") (pin "29") (pinfunction "PA20/EIC/SCOM5PAD2+_29") (pintype "bidirectional"))
    )
    (net (code "70") (name "unconnected-(U2-PA21{slash}EIC{slash}SCOM5PAD3+-Pad30)") (class "Default")
      (node (ref "U2") (pin "30") (pinfunction "PA21/EIC/SCOM5PAD3+_30") (pintype "bidirectional"))
    )
    (net (code "71") (name "unconnected-(U2-PA24{slash}EIC{slash}SCOM3PAD2+{slash}TC5-Pad33)") (class "Default")
      (node (ref "U2") (pin "33") (pinfunction "PA24/EIC/SCOM3PAD2+/TC5_33") (pintype "bidirectional"))
    )
    (net (code "72") (name "unconnected-(U2-PA25{slash}EIC{slash}SCOM3PAD3+{slash}TC5-Pad34)") (class "Default")
      (node (ref "U2") (pin "34") (pinfunction "PA25/EIC/SCOM3PAD3+/TC5_34") (pintype "bidirectional"))
    )
    (net (code "73") (name "unconnected-(U2-PA28{slash}EIC-Pad41)") (class "Default")
      (node (ref "U2") (pin "41") (pinfunction "PA28/EIC_41") (pintype "bidirectional"))
    )
    (net (code "74") (name "unconnected-(U2-PB09{slash}EIC{slash}AIN3{slash}SCOM4PAD1{slash}{slash}TC4-Pad8)") (class "Default")
      (node (ref "U2") (pin "8") (pinfunction "PB09/EIC/AIN3/SCOM4PAD1//TC4_8") (pintype "bidirectional"))
    )
    (net (code "75") (name "unconnected-(U2-PB22{slash}EIC{slash}SCOM5PAD2-Pad37)") (class "Default")
      (node (ref "U2") (pin "37") (pinfunction "PB22/EIC/SCOM5PAD2_37") (pintype "bidirectional"))
    )
    (net (code "76") (name "unconnected-(U2-PB23{slash}EIC{slash}SCOM5PAD3-Pad38)") (class "Default")
      (node (ref "U2") (pin "38") (pinfunction "PB23/EIC/SCOM5PAD3_38") (pintype "bidirectional"))
    )
    (net (code "77") (name "unconnected-(U5-32KHZ-Pad1)") (class "Default")
      (node (ref "U5") (pin "1") (pinfunction "32KHZ_1") (pintype "bidirectional"))
    )
    (net (code "78") (name "unconnected-(U5-~{RST}-Pad4)") (class "Default")
      (node (ref "U5") (pin "4") (pinfunction "~{RST}_4") (pintype "bidirectional"))
    )
    (net (code "79") (name "unconnected-(U7-CSB1-Pad16)") (class "Default")
      (node (ref "U7") (pin "16") (pinfunction "CSB1_16") (pintype "bidirectional"))
    )
    (net (code "80") (name "unconnected-(U7-CSB2-Pad5)") (class "Default")
      (node (ref "U7") (pin "5") (pinfunction "CSB2_5") (pintype "bidirectional"))
    )
    (net (code "81") (name "unconnected-(U7-NC-Pad8)") (class "Default")
      (node (ref "U7") (pin "8") (pinfunction "NC_8") (pintype "no_connect"))
    )
    (net (code "82") (name "unconnected-(U7-NC-Pad18)") (class "Default")
      (node (ref "U7") (pin "18") (pinfunction "NC_18") (pintype "no_connect"))
    )
    (net (code "83") (name "unconnected-(U8-NC-Pad10)") (class "Default")
      (node (ref "U8") (pin "10") (pinfunction "NC_10") (pintype "no_connect"))
    )
    (net (code "84") (name "unconnected-(U8-RES-Pad3)") (class "Default")
      (node (ref "U8") (pin "3") (pinfunction "RES_3") (pintype "bidirectional"))
    )
    (net (code "85") (name "unconnected-(U8-RES-Pad11)") (class "Default")
      (node (ref "U8") (pin "11") (pinfunction "RES_11") (pintype "bidirectional"))
    )
    (net (code "86") (name "unconnected-(U9-P06-Pad7)") (class "Default")
      (node (ref "U9") (pin "7") (pinfunction "P06_7") (pintype "bidirectional"))
    )
    (net (code "87") (name "unconnected-(U9-P07-Pad8)") (class "Default")
      (node (ref "U9") (pin "8") (pinfunction "P07_8") (pintype "bidirectional"))
    )
    (net (code "88") (name "unconnected-(U9-P10-Pad10)") (class "Default")
      (node (ref "U9") (pin "10") (pinfunction "P10_10") (pintype "bidirectional"))
    )
    (net (code "89") (name "unconnected-(U9-P11-Pad11)") (class "Default")
      (node (ref "U9") (pin "11") (pinfunction "P11_11") (pintype "bidirectional"))
    )
    (net (code "90") (name "unconnected-(U9-P12-Pad12)") (class "Default")
      (node (ref "U9") (pin "12") (pinfunction "P12_12") (pintype "bidirectional"))
    )
    (net (code "91") (name "unconnected-(U9-P13-Pad13)") (class "Default")
      (node (ref "U9") (pin "13") (pinfunction "P13_13") (pintype "bidirectional"))
    )
    (net (code "92") (name "unconnected-(U9-P14-Pad14)") (class "Default")
      (node (ref "U9") (pin "14") (pinfunction "P14_14") (pintype "bidirectional"))
    )
    (net (code "93") (name "unconnected-(U9-P15-Pad15)") (class "Default")
      (node (ref "U9") (pin "15") (pinfunction "P15_15") (pintype "bidirectional"))
    )
    (net (code "94") (name "unconnected-(U9-P16-Pad16)") (class "Default")
      (node (ref "U9") (pin "16") (pinfunction "P16_16") (pintype "bidirectional"))
    )
    (net (code "95") (name "unconnected-(U9-P17-Pad17)") (class "Default")
      (node (ref "U9") (pin "17") (pinfunction "P17_17") (pintype "bidirectional"))
    )
    (net (code "96") (name "unconnected-(U11-ALM_HI-PadP$8)") (class "Default")
      (node (ref "U11") (pin "P$8") (pinfunction "ALM_HI_P$8") (pintype "bidirectional"))
    )
    (net (code "97") (name "unconnected-(U11-ALM_LO-PadP$1)") (class "Default")
      (node (ref "U11") (pin "P$1") (pinfunction "ALM_LO_P$1") (pintype "bidirectional"))
    )
    (net (code "98") (name "unconnected-(U11-RDY-PadP$2)") (class "Default")
      (node (ref "U11") (pin "P$2") (pinfunction "RDY_P$2") (pintype "bidirectional"))
    )
    (net (code "99") (name "unconnected-(U12-NC-Pad5)") (class "Default")
      (node (ref "U12") (pin "5") (pinfunction "NC_5") (pintype "no_connect"))
    )
    (net (code "100") (name "unconnected-(U12-NC-Pad6)") (class "Default")
      (node (ref "U12") (pin "6") (pinfunction "NC_6") (pintype "no_connect"))
    )
    (net (code "101") (name "unconnected-(U12-NC-Pad7)") (class "Default")
      (node (ref "U12") (pin "7") (pinfunction "NC_7") (pintype "no_connect"))
    )
    (net (code "102") (name "unconnected-(U12-NC-Pad8)") (class "Default")
      (node (ref "U12") (pin "8") (pinfunction "NC_8") (pintype "no_connect"))
    )
  )
)
